# iGlass_v3.net
KiCad netlist of a schematic drawn in EAGLE
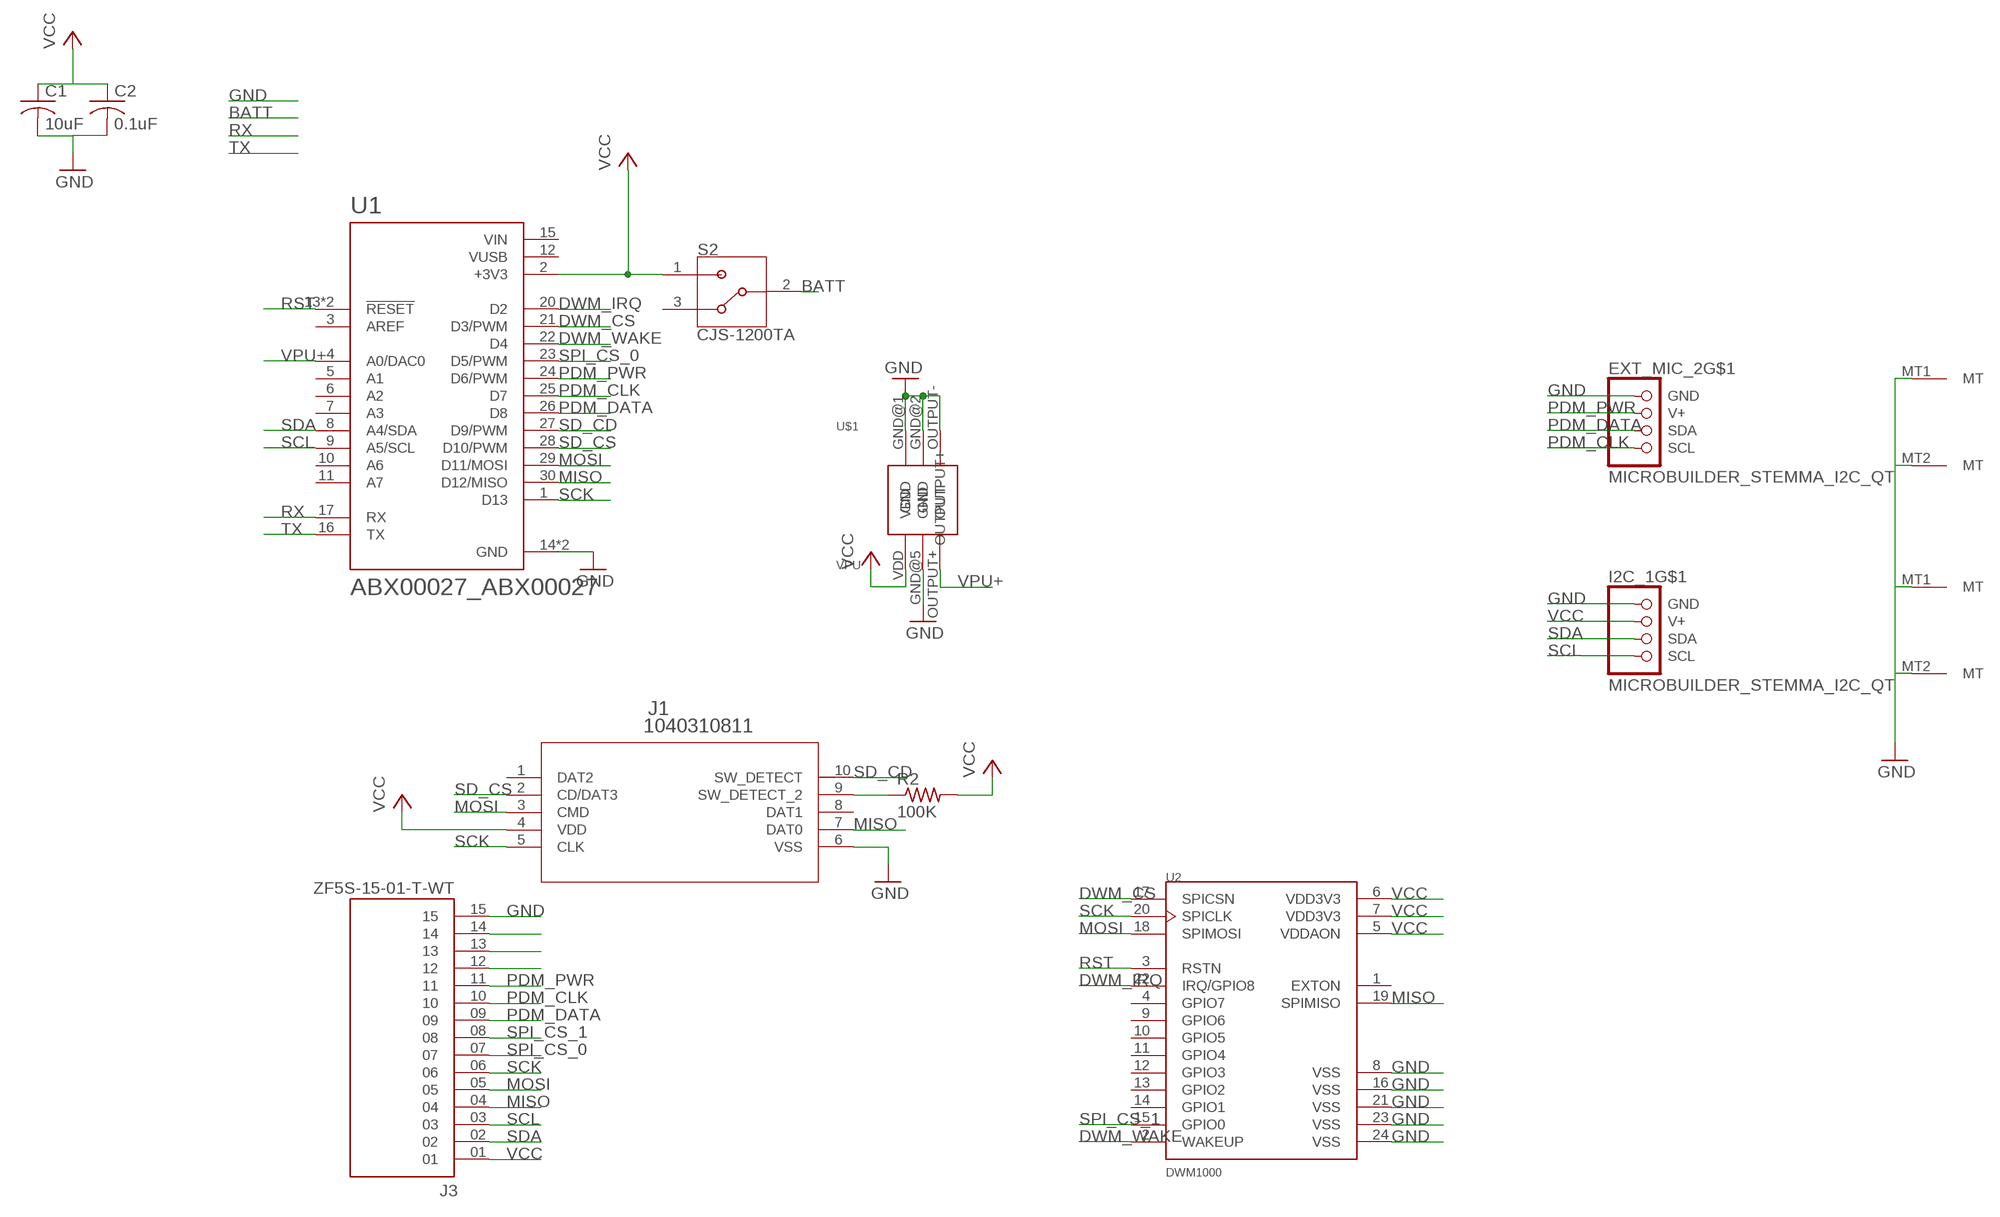
[diagram p0: schematic, sheet 1]

(export (version "E")
  (design (tool "Eeschema 10.0.6"))
  (components
    (comp (ref "C1")
      (value "10uF")
      (footprint "eagle-import:C0805")
      (libsource (lib "eagle-import") (part "C-USC0805"))
    )
    (comp (ref "C2")
      (value "0.1uF")
      (footprint "eagle-import:C0805")
      (libsource (lib "eagle-import") (part "C-USC0805"))
    )
    (comp (ref "EXT_MIC_2")
      (value "MICROBUILDER_STEMMA_I2C_QT")
      (footprint "eagle-import:MICROBUILDER_JST_SH4")
      (libsource (lib "eagle-import") (part "MICROBUILDER_STEMMA_I2C_QT"))
    )
    (comp (ref "I2C_1")
      (value "MICROBUILDER_STEMMA_I2C_QT")
      (footprint "eagle-import:MICROBUILDER_JST_SH4")
      (libsource (lib "eagle-import") (part "MICROBUILDER_STEMMA_I2C_QT"))
    )
    (comp (ref "J1")
      (value "1040310811")
      (footprint "eagle-import:104031-0811_MOL")
      (fields (field (name "COPYRIGHT") "Copyright (C) 2021 Ultra Librarian. All rights reserved."))
      (libsource (lib "eagle-import") (part "1040310811"))
    )
    (comp (ref "J3")
      (value "ZF5S-15-01-T-WT")
      (footprint "eagle-import:SAMTEC_ZF5S-15-01-T-WT")
      (fields (field (name "MANUFACTURER") "SAMTEC "))
      (libsource (lib "eagle-import") (part "ZF5S-15-01-T-WT"))
    )
    (comp (ref "R2")
      (value "100K")
      (footprint "eagle-import:R0805")
      (libsource (lib "eagle-import") (part "R-US_R0805"))
    )
    (comp (ref "S2")
      (value "CJS-1200TA")
      (footprint "eagle-import:SW_CJS-1200TA")
      (fields (field (name "MF") "Nidec Copal"))
      (libsource (lib "eagle-import") (part "CJS-1200TA"))
    )
    (comp (ref "U$1")
      (value "VPU")
      (footprint "eagle-import:VPU")
      (libsource (lib "eagle-import") (part "VPU"))
    )
    (comp (ref "U1")
      (value "ABX00027_ABX00027")
      (footprint "eagle-import:ABX00027_MODULE_ABX00027")
      (fields (field (name "MF") "Arduino") (field (name "MP") "ABX00027"))
      (libsource (lib "eagle-import") (part "ABX00027_ABX00027"))
    )
    (comp (ref "U2")
      (value "DWM1000")
      (footprint "eagle-import:XCVR_DWM1000")
      (fields (field (name "MF") "Qorvo"))
      (libsource (lib "eagle-import") (part "DWM1000"))
    )
  )
  (nets
    (net (code "1") (name "/BATT") (class "Default")
      (node (ref "S2") (pin "2") (pinfunction "2_2") (pintype "passive"))
    )
    (net (code "2") (name "/DWM_CS") (class "Default")
      (node (ref "U1") (pin "21") (pinfunction "D3/PWM_21") (pintype "bidirectional"))
      (node (ref "U2") (pin "17") (pinfunction "SPICSN_17") (pintype "input"))
    )
    (net (code "3") (name "/DWM_IRQ") (class "Default")
      (node (ref "U1") (pin "20") (pinfunction "D2_20") (pintype "bidirectional"))
      (node (ref "U2") (pin "22") (pinfunction "IRQ/GPIO8_22") (pintype "bidirectional"))
    )
    (net (code "4") (name "/DWM_WAKE") (class "Default")
      (node (ref "U1") (pin "22") (pinfunction "D4_22") (pintype "bidirectional"))
      (node (ref "U2") (pin "2") (pinfunction "WAKEUP_2") (pintype "bidirectional"))
    )
    (net (code "5") (name "/MISO") (class "Default")
      (node (ref "J1") (pin "7") (pinfunction "DAT0_7") (pintype "bidirectional"))
      (node (ref "J3") (pin "04") (pinfunction "04_04") (pintype "passive"))
      (node (ref "U1") (pin "30") (pinfunction "D12/MISO_30") (pintype "bidirectional"))
      (node (ref "U2") (pin "19") (pinfunction "SPIMISO_19") (pintype "output"))
    )
    (net (code "6") (name "/MOSI") (class "Default")
      (node (ref "J1") (pin "3") (pinfunction "CMD_3") (pintype "passive"))
      (node (ref "J3") (pin "05") (pinfunction "05_05") (pintype "passive"))
      (node (ref "U1") (pin "29") (pinfunction "D11/MOSI_29") (pintype "bidirectional"))
      (node (ref "U2") (pin "18") (pinfunction "SPIMOSI_18") (pintype "input"))
    )
    (net (code "7") (name "/PDM_CLK") (class "Default")
      (node (ref "EXT_MIC_2") (pin "4") (pinfunction "SCL_4") (pintype "passive"))
      (node (ref "J3") (pin "10") (pinfunction "10_10") (pintype "passive"))
      (node (ref "U1") (pin "25") (pinfunction "D7_25") (pintype "bidirectional"))
    )
    (net (code "8") (name "/PDM_DATA") (class "Default")
      (node (ref "EXT_MIC_2") (pin "3") (pinfunction "SDA_3") (pintype "passive"))
      (node (ref "J3") (pin "09") (pinfunction "09_09") (pintype "passive"))
      (node (ref "U1") (pin "26") (pinfunction "D8_26") (pintype "bidirectional"))
    )
    (net (code "9") (name "/PDM_PWR") (class "Default")
      (node (ref "EXT_MIC_2") (pin "2") (pinfunction "V+_2") (pintype "passive"))
      (node (ref "J3") (pin "11") (pinfunction "11_11") (pintype "passive"))
      (node (ref "U1") (pin "24") (pinfunction "D6/PWM_24") (pintype "bidirectional"))
    )
    (net (code "10") (name "/RST") (class "Default")
      (node (ref "U1") (pin "13") (pinfunction "~{RESET}_13") (pintype "input"))
      (node (ref "U1") (pin "18") (pinfunction "~{RESET}_18") (pintype "input"))
      (node (ref "U2") (pin "3") (pinfunction "RSTN_3") (pintype "bidirectional"))
    )
    (net (code "11") (name "/RX") (class "Default")
      (node (ref "U1") (pin "17") (pinfunction "RX_17") (pintype "bidirectional"))
    )
    (net (code "12") (name "/SCK") (class "Default")
      (node (ref "J1") (pin "5") (pinfunction "CLK_5") (pintype "passive"))
      (node (ref "J3") (pin "06") (pinfunction "06_06") (pintype "passive"))
      (node (ref "U1") (pin "1") (pinfunction "D13_1") (pintype "bidirectional"))
      (node (ref "U2") (pin "20") (pinfunction "SPICLK_20") (pintype "input"))
    )
    (net (code "13") (name "/SCL") (class "Default")
      (node (ref "I2C_1") (pin "4") (pinfunction "SCL_4") (pintype "passive"))
      (node (ref "J3") (pin "03") (pinfunction "03_03") (pintype "passive"))
      (node (ref "U1") (pin "9") (pinfunction "A5/SCL_9") (pintype "input"))
    )
    (net (code "14") (name "/SDA") (class "Default")
      (node (ref "I2C_1") (pin "3") (pinfunction "SDA_3") (pintype "passive"))
      (node (ref "J3") (pin "02") (pinfunction "02_02") (pintype "passive"))
      (node (ref "U1") (pin "8") (pinfunction "A4/SDA_8") (pintype "input"))
    )
    (net (code "15") (name "/SD_CD") (class "Default")
      (node (ref "J1") (pin "10") (pinfunction "SW_DETECT_10") (pintype "passive"))
      (node (ref "U1") (pin "27") (pinfunction "D9/PWM_27") (pintype "bidirectional"))
    )
    (net (code "16") (name "/SD_CS") (class "Default")
      (node (ref "J1") (pin "2") (pinfunction "CD/DAT3_2") (pintype "bidirectional"))
      (node (ref "U1") (pin "28") (pinfunction "D10/PWM_28") (pintype "bidirectional"))
    )
    (net (code "17") (name "/SPI_CS_0") (class "Default")
      (node (ref "J3") (pin "07") (pinfunction "07_07") (pintype "passive"))
      (node (ref "U1") (pin "23") (pinfunction "D5/PWM_23") (pintype "bidirectional"))
    )
    (net (code "18") (name "/SPI_CS_1") (class "Default")
      (node (ref "J3") (pin "08") (pinfunction "08_08") (pintype "passive"))
      (node (ref "U2") (pin "15") (pinfunction "GPIO0_15") (pintype "bidirectional"))
    )
    (net (code "19") (name "/TX") (class "Default")
      (node (ref "U1") (pin "16") (pinfunction "TX_16") (pintype "bidirectional"))
    )
    (net (code "20") (name "/VIN") (class "Default")
      (node (ref "U1") (pin "15") (pinfunction "VIN_15") (pintype "power_in"))
    )
    (net (code "21") (name "/VPU+") (class "Default")
      (node (ref "U$1") (pin "OUTPUT+") (pinfunction "OUTPUT+_OUTPUT+") (pintype "output"))
      (node (ref "U1") (pin "4") (pinfunction "A0/DAC0_4") (pintype "bidirectional"))
    )
    (net (code "22") (name "/VUSB") (class "Default")
      (node (ref "U1") (pin "12") (pinfunction "VUSB_12") (pintype "power_in"))
    )
    (net (code "23") (name "GND") (class "Default")
      (node (ref "C1") (pin "2") (pinfunction "2_2") (pintype "passive"))
      (node (ref "C2") (pin "2") (pinfunction "2_2") (pintype "passive"))
      (node (ref "EXT_MIC_2") (pin "1") (pinfunction "GND_1") (pintype "passive"))
      (node (ref "EXT_MIC_2") (pin "MT1") (pinfunction "MT_MT1") (pintype "bidirectional"))
      (node (ref "EXT_MIC_2") (pin "MT2") (pinfunction "MT_MT2") (pintype "bidirectional"))
      (node (ref "I2C_1") (pin "1") (pinfunction "GND_1") (pintype "passive"))
      (node (ref "I2C_1") (pin "MT1") (pinfunction "MT_MT1") (pintype "bidirectional"))
      (node (ref "I2C_1") (pin "MT2") (pinfunction "MT_MT2") (pintype "bidirectional"))
      (node (ref "J1") (pin "6") (pinfunction "VSS_6") (pintype "passive"))
      (node (ref "J3") (pin "14") (pinfunction "14_14") (pintype "passive"))
      (node (ref "J3") (pin "15") (pinfunction "15_15") (pintype "passive"))
      (node (ref "U$1") (pin "GND@1") (pinfunction "GND_GND@1") (pintype "power_in"))
      (node (ref "U$1") (pin "GND@2") (pinfunction "GND_GND@2") (pintype "power_in"))
      (node (ref "U$1") (pin "GND@5") (pinfunction "GND_GND@5") (pintype "power_in"))
      (node (ref "U$1") (pin "OUTPUT-") (pinfunction "OUTPUT-_OUTPUT-") (pintype "output"))
      (node (ref "U1") (pin "14") (pinfunction "GND_14") (pintype "power_in"))
      (node (ref "U1") (pin "19") (pinfunction "GND_19") (pintype "power_in"))
      (node (ref "U2") (pin "16") (pinfunction "VSS_16") (pintype "power_in"))
      (node (ref "U2") (pin "21") (pinfunction "VSS_21") (pintype "power_in"))
      (node (ref "U2") (pin "23") (pinfunction "VSS_23") (pintype "power_in"))
      (node (ref "U2") (pin "24") (pinfunction "VSS_24") (pintype "power_in"))
      (node (ref "U2") (pin "8") (pinfunction "VSS_8") (pintype "power_in"))
    )
    (net (code "24") (name "Net-(J1-SW_DETECT_2)") (class "Default")
      (node (ref "J1") (pin "9") (pinfunction "SW_DETECT_2_9") (pintype "passive"))
      (node (ref "R2") (pin "1") (pinfunction "1_1") (pintype "passive"))
    )
    (net (code "25") (name "VCC") (class "Default")
      (node (ref "C1") (pin "1") (pinfunction "1_1") (pintype "passive"))
      (node (ref "C2") (pin "1") (pinfunction "1_1") (pintype "passive"))
      (node (ref "I2C_1") (pin "2") (pinfunction "V+_2") (pintype "passive"))
      (node (ref "J1") (pin "4") (pinfunction "VDD_4") (pintype "power_in"))
      (node (ref "J3") (pin "01") (pinfunction "01_01") (pintype "passive"))
      (node (ref "R2") (pin "2") (pinfunction "2_2") (pintype "passive"))
      (node (ref "S2") (pin "1") (pinfunction "1_1") (pintype "passive"))
      (node (ref "U$1") (pin "VDD") (pinfunction "VDD_VDD") (pintype "power_in"))
      (node (ref "U1") (pin "2") (pinfunction "+3V3_2") (pintype "power_in"))
      (node (ref "U2") (pin "5") (pinfunction "VDDAON_5") (pintype "power_in"))
      (node (ref "U2") (pin "6") (pinfunction "VDD3V3_6") (pintype "power_in"))
      (node (ref "U2") (pin "7") (pinfunction "VDD3V3_7") (pintype "power_in"))
    )
    (net (code "26") (name "unconnected-(J1-DAT1-Pad8)") (class "Default")
      (node (ref "J1") (pin "8") (pinfunction "DAT1_8") (pintype "bidirectional"))
    )
    (net (code "27") (name "unconnected-(J1-DAT2-Pad1)") (class "Default")
      (node (ref "J1") (pin "1") (pinfunction "DAT2_1") (pintype "bidirectional"))
    )
    (net (code "28") (name "unconnected-(J3-Pad12)") (class "Default")
      (node (ref "J3") (pin "12") (pinfunction "12_12") (pintype "passive"))
    )
    (net (code "29") (name "unconnected-(J3-Pad13)") (class "Default")
      (node (ref "J3") (pin "13") (pinfunction "13_13") (pintype "passive"))
    )
    (net (code "30") (name "unconnected-(S2-Pad3)") (class "Default")
      (node (ref "S2") (pin "3") (pinfunction "3_3") (pintype "passive"))
    )
    (net (code "31") (name "unconnected-(U1-A1-Pad5)") (class "Default")
      (node (ref "U1") (pin "5") (pinfunction "A1_5") (pintype "input"))
    )
    (net (code "32") (name "unconnected-(U1-A2-Pad6)") (class "Default")
      (node (ref "U1") (pin "6") (pinfunction "A2_6") (pintype "input"))
    )
    (net (code "33") (name "unconnected-(U1-A3-Pad7)") (class "Default")
      (node (ref "U1") (pin "7") (pinfunction "A3_7") (pintype "input"))
    )
    (net (code "34") (name "unconnected-(U1-A6-Pad10)") (class "Default")
      (node (ref "U1") (pin "10") (pinfunction "A6_10") (pintype "input"))
    )
    (net (code "35") (name "unconnected-(U1-A7-Pad11)") (class "Default")
      (node (ref "U1") (pin "11") (pinfunction "A7_11") (pintype "input"))
    )
    (net (code "36") (name "unconnected-(U1-AREF-Pad3)") (class "Default")
      (node (ref "U1") (pin "3") (pinfunction "AREF_3") (pintype "input"))
    )
    (net (code "37") (name "unconnected-(U2-EXTON-Pad1)") (class "Default")
      (node (ref "U2") (pin "1") (pinfunction "EXTON_1") (pintype "output"))
    )
    (net (code "38") (name "unconnected-(U2-GPIO1-Pad14)") (class "Default")
      (node (ref "U2") (pin "14") (pinfunction "GPIO1_14") (pintype "bidirectional"))
    )
    (net (code "39") (name "unconnected-(U2-GPIO2-Pad13)") (class "Default")
      (node (ref "U2") (pin "13") (pinfunction "GPIO2_13") (pintype "bidirectional"))
    )
    (net (code "40") (name "unconnected-(U2-GPIO3-Pad12)") (class "Default")
      (node (ref "U2") (pin "12") (pinfunction "GPIO3_12") (pintype "bidirectional"))
    )
    (net (code "41") (name "unconnected-(U2-GPIO4-Pad11)") (class "Default")
      (node (ref "U2") (pin "11") (pinfunction "GPIO4_11") (pintype "bidirectional"))
    )
    (net (code "42") (name "unconnected-(U2-GPIO5-Pad10)") (class "Default")
      (node (ref "U2") (pin "10") (pinfunction "GPIO5_10") (pintype "bidirectional"))
    )
    (net (code "43") (name "unconnected-(U2-GPIO6-Pad9)") (class "Default")
      (node (ref "U2") (pin "9") (pinfunction "GPIO6_9") (pintype "bidirectional"))
    )
    (net (code "44") (name "unconnected-(U2-GPIO7-Pad4)") (class "Default")
      (node (ref "U2") (pin "4") (pinfunction "GPIO7_4") (pintype "bidirectional"))
    )
  )
)
